# stm32.net
KiCad netlist of a schematic drawn in Altium Designer
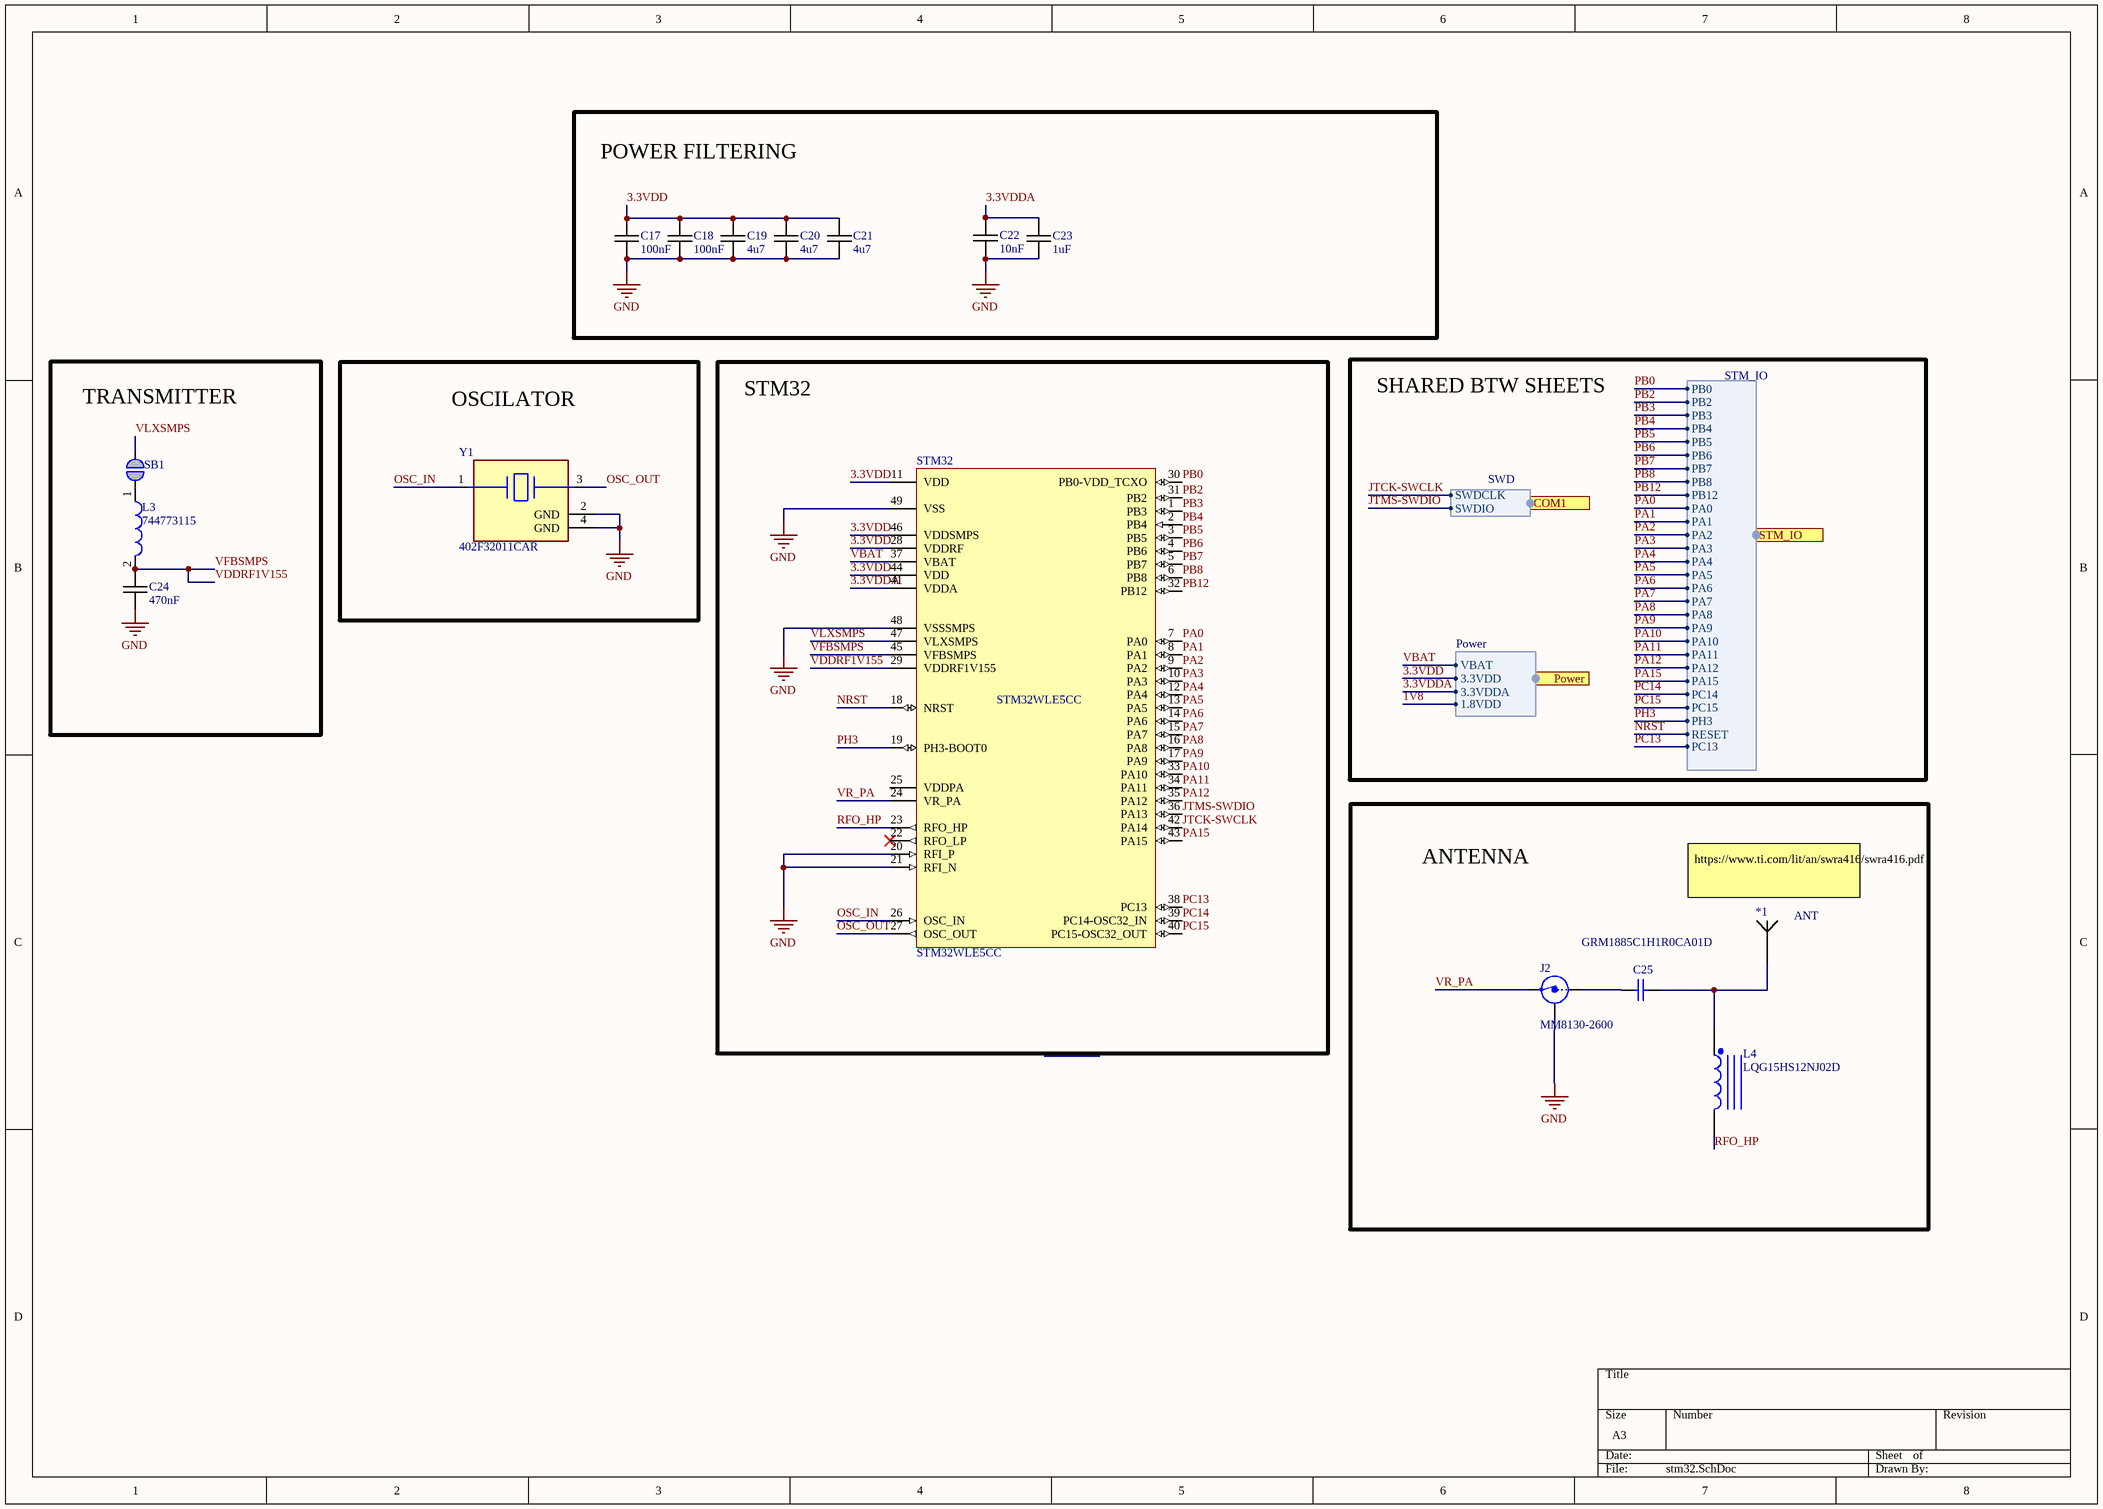
[diagram p0: stm32.SchDoc]

(export (version "E")
  (design (tool "Eeschema 10.0.6"))
  (components
    (comp (ref "*1") (value "ANT") (libsource (lib "FEEL-Lora-STM32-Road-datalogger") (part "ANT")))
    (comp (ref "C17")
      (value "100nF")
      (footprint "0603C-GENERIC")
      (description "CAPACITOR 0603 CERAMIC")
      (fields (field (name "TOLERANCE") "±10%") (field (name "MANUFACTURER PART NUMBER") "C1608X7R1H103K"))
      (libsource (lib "vh_altium_library") (part "0603C-100NF-50V-X7R-TDK"))
    )
    (comp (ref "C18")
      (value "100nF")
      (footprint "0603C-GENERIC")
      (description "CAPACITOR 0603 CERAMIC")
      (fields (field (name "TOLERANCE") "±10%") (field (name "MANUFACTURER PART NUMBER") "C1608X7R1H103K"))
      (libsource (lib "vh_altium_library") (part "0603C-100NF-50V-X7R-TDK"))
    )
    (comp (ref "C19")
      (value "4u7")
      (footprint "0603C-GENERIC")
      (description "CAPACITOR 0603 CERAMIC")
      (libsource (lib "vh_altium_library") (part "0603C-4U7-6V3-X5R-KEM"))
    )
    (comp (ref "C20")
      (value "4u7")
      (footprint "0603C-GENERIC")
      (description "CAPACITOR 0603 CERAMIC")
      (libsource (lib "vh_altium_library") (part "0603C-4U7-6V3-X5R-KEM"))
    )
    (comp (ref "C21")
      (value "4u7")
      (footprint "0603C-GENERIC")
      (description "CAPACITOR 0603 CERAMIC")
      (libsource (lib "vh_altium_library") (part "0603C-4U7-6V3-X5R-KEM"))
    )
    (comp (ref "C22")
      (value "10nF")
      (footprint "0603C-GENERIC")
      (description "CAPACITOR 0603 CERAMIC")
      (fields
        (field (name "MANUFACTURER PART NUMBER") "GRM188R71H103KA01D")
        (field (name "MANUFACTURER") "Murata Electronics North America")
      )
      (libsource (lib "vh_altium_library") (part "0603C-10NF-50V-X7R-MUR"))
    )
    (comp (ref "C23")
      (value "1uF")
      (footprint "0603C-GENERIC")
      (description "CAPACITOR 0603 CERAMIC")
      (libsource (lib "vh_altium_library") (part "0603C-1UF-25V-X5R-SAM"))
    )
    (comp (ref "C24")
      (value "470nF")
      (footprint "0603C-GENERIC")
      (description "CAPACITOR 0603 CERAMIC")
      (fields
        (field (name "MANUFACTURER") "Murata Electronics North America")
        (field (name "TOLERANCE") "±10%")
      )
      (libsource (lib "vh_altium_library") (part "0603C-470NF-25V-X7R-MUR"))
    )
    (comp (ref "C25")
      (value "GRM1885C1H1R0CA01D")
      (footprint "CAPC1608X90X35NL10T15")
      (fields (field (name "MANUFACTURER") "Murata"))
      (libsource (lib "Altium Content Vault") (part "CAP"))
    )
    (comp (ref "J2")
      (value "MM8130-2600")
      (footprint "COAXIAL-SWF")
      (description "Coaxial Connector with Switch")
      (fields (field (name "MANUFACTURER") "Murata") (field (name "PUBLISHER") "Nordic Semiconductor"))
      (libsource (lib "FEEL2020") (part "MM8130-2600"))
    )
    (comp (ref "L3")
      (value "744773115")
      (footprint "WE-PD2-S")
      (description "SMD Power Inductor WE-PD2, L = 15.0 µH")
      (libsource (lib "Altium Content Vault") (part "PAS-IND-INDUCTOR-2"))
    )
    (comp (ref "L4")
      (value "LQG15HS12NJ02D")
      (footprint "INDC1005X55X25LL05T10_A")
      (description "Chip Inductor, 12 nH, +/-5%, 300 mA, -55 to 125 degC, 0402 (1005 Metric), RoHS, Tape and Reel")
      (fields (field (name "MANUFACTURER") "Murata"))
      (libsource (lib "Altium Content Vault") (part "IND-DOT-2"))
    )
    (comp (ref "SB1")
      (value "Solderbridge")
      (footprint "Solderbridge")
      (fields (field (name "PUBLISHER") "Nordic Semiconductor"))
      (libsource (lib "FEEL2020") (part "SOLDERBRIDGE"))
    )
    (comp (ref "STM32")
      (value "STM32WLE5CC")
      (footprint "stm32wle5cc")
      (description "Ultra-low power multi-modulation wireless STM32WLE5 microcontrollers")
      (libsource (lib "FEEL-Lora-STM32-Road-datalogger") (part "STM32WLE5CC"))
    )
    (comp (ref "Y1")
      (value "402F32011CAR")
      (footprint "FP-402-MFG")
      (description "CRYSTAL 32.0000MHZ 10PF SMD")
      (fields (field (name "TOLERANCE") "10ppm"))
      (libsource (lib "Altium Content Vault") (part "aa2bcc763e4d5c877d8ff97ea4c95a3"))
    )
  )
  (nets
    (net (code "5") (name "/3.3VDD") (class "Default")
      (node (ref "C17") (pin "1") (pintype "passive"))
      (node (ref "C18") (pin "1") (pintype "passive"))
      (node (ref "C19") (pin "1") (pintype "passive"))
      (node (ref "C20") (pin "1") (pintype "passive"))
      (node (ref "C21") (pin "1") (pintype "passive"))
      (node (ref "STM32") (pin "11") (pinfunction "VDD_11") (pintype "power_in"))
      (node (ref "STM32") (pin "28") (pinfunction "VDDRF_28") (pintype "power_in"))
      (node (ref "STM32") (pin "44") (pinfunction "VDD_44") (pintype "power_in"))
      (node (ref "STM32") (pin "46") (pinfunction "VDDSMPS_46") (pintype "power_in"))
    )
    (net (code "6") (name "/3.3VDDA") (class "Default")
      (node (ref "C22") (pin "1") (pintype "passive"))
      (node (ref "C23") (pin "1") (pintype "passive"))
      (node (ref "STM32") (pin "41") (pinfunction "VDDA_41") (pintype "power_in"))
    )
    (net (code "7") (name "/JTCK-SWCLK") (class "Default")
      (node (ref "STM32") (pin "42") (pinfunction "PA14_42") (pintype "bidirectional"))
    )
    (net (code "8") (name "/JTMS-SWDIO") (class "Default")
      (node (ref "STM32") (pin "36") (pinfunction "PA13_36") (pintype "bidirectional"))
    )
    (net (code "9") (name "/NRST") (class "Default")
      (node (ref "STM32") (pin "18") (pinfunction "NRST_18") (pintype "bidirectional"))
    )
    (net (code "10") (name "/OSC_IN") (class "Default")
      (node (ref "STM32") (pin "26") (pinfunction "OSC_IN_26") (pintype "input"))
      (node (ref "Y1") (pin "1") (pinfunction "1_1") (pintype "passive"))
    )
    (net (code "11") (name "/OSC_OUT") (class "Default")
      (node (ref "STM32") (pin "27") (pinfunction "OSC_OUT_27") (pintype "output"))
      (node (ref "Y1") (pin "3") (pinfunction "3_3") (pintype "passive"))
    )
    (net (code "12") (name "/PA0") (class "Default")
      (node (ref "STM32") (pin "7") (pinfunction "PA0_7") (pintype "bidirectional"))
    )
    (net (code "13") (name "/PA1") (class "Default")
      (node (ref "STM32") (pin "8") (pinfunction "PA1_8") (pintype "bidirectional"))
    )
    (net (code "14") (name "/PA2") (class "Default")
      (node (ref "STM32") (pin "9") (pinfunction "PA2_9") (pintype "bidirectional"))
    )
    (net (code "15") (name "/PA3") (class "Default")
      (node (ref "STM32") (pin "10") (pinfunction "PA3_10") (pintype "bidirectional"))
    )
    (net (code "16") (name "/PA4") (class "Default")
      (node (ref "STM32") (pin "12") (pinfunction "PA4_12") (pintype "bidirectional"))
    )
    (net (code "17") (name "/PA5") (class "Default")
      (node (ref "STM32") (pin "13") (pinfunction "PA5_13") (pintype "bidirectional"))
    )
    (net (code "18") (name "/PA6") (class "Default")
      (node (ref "STM32") (pin "14") (pinfunction "PA6_14") (pintype "bidirectional"))
    )
    (net (code "19") (name "/PA7") (class "Default")
      (node (ref "STM32") (pin "15") (pinfunction "PA7_15") (pintype "bidirectional"))
    )
    (net (code "20") (name "/PA8") (class "Default")
      (node (ref "STM32") (pin "16") (pinfunction "PA8_16") (pintype "bidirectional"))
    )
    (net (code "21") (name "/PA9") (class "Default")
      (node (ref "STM32") (pin "17") (pinfunction "PA9_17") (pintype "bidirectional"))
    )
    (net (code "22") (name "/PA10") (class "Default")
      (node (ref "STM32") (pin "33") (pinfunction "PA10_33") (pintype "bidirectional"))
    )
    (net (code "23") (name "/PA11") (class "Default")
      (node (ref "STM32") (pin "34") (pinfunction "PA11_34") (pintype "bidirectional"))
    )
    (net (code "24") (name "/PA12") (class "Default")
      (node (ref "STM32") (pin "35") (pinfunction "PA12_35") (pintype "bidirectional"))
    )
    (net (code "25") (name "/PA15") (class "Default")
      (node (ref "STM32") (pin "43") (pinfunction "PA15_43") (pintype "bidirectional"))
    )
    (net (code "26") (name "/PB0") (class "Default")
      (node (ref "STM32") (pin "30") (pinfunction "PB0-VDD_TCXO_30") (pintype "bidirectional"))
    )
    (net (code "27") (name "/PB2") (class "Default")
      (node (ref "STM32") (pin "31") (pinfunction "PB2_31") (pintype "bidirectional"))
    )
    (net (code "28") (name "/PB3") (class "Default")
      (node (ref "STM32") (pin "1") (pinfunction "PB3_1") (pintype "bidirectional"))
    )
    (net (code "29") (name "/PB4") (class "Default")
      (node (ref "STM32") (pin "2") (pinfunction "PB4_2") (pintype "input"))
    )
    (net (code "30") (name "/PB5") (class "Default")
      (node (ref "STM32") (pin "3") (pinfunction "PB5_3") (pintype "bidirectional"))
    )
    (net (code "31") (name "/PB6") (class "Default")
      (node (ref "STM32") (pin "4") (pinfunction "PB6_4") (pintype "bidirectional"))
    )
    (net (code "32") (name "/PB7") (class "Default")
      (node (ref "STM32") (pin "5") (pinfunction "PB7_5") (pintype "bidirectional"))
    )
    (net (code "33") (name "/PB8") (class "Default")
      (node (ref "STM32") (pin "6") (pinfunction "PB8_6") (pintype "bidirectional"))
    )
    (net (code "34") (name "/PB12") (class "Default")
      (node (ref "STM32") (pin "32") (pinfunction "PB12_32") (pintype "bidirectional"))
    )
    (net (code "35") (name "/PC13") (class "Default")
      (node (ref "STM32") (pin "38") (pinfunction "PC13_38") (pintype "bidirectional"))
    )
    (net (code "36") (name "/PC14") (class "Default")
      (node (ref "STM32") (pin "39") (pinfunction "PC14-OSC32_IN_39") (pintype "bidirectional"))
    )
    (net (code "37") (name "/PC15") (class "Default")
      (node (ref "STM32") (pin "40") (pinfunction "PC15-OSC32_OUT_40") (pintype "bidirectional"))
    )
    (net (code "38") (name "/PH3") (class "Default")
      (node (ref "STM32") (pin "19") (pinfunction "PH3-BOOT0_19") (pintype "bidirectional"))
    )
    (net (code "39") (name "/RFO_HP") (class "Default")
      (node (ref "L4") (pin "2") (pinfunction "2_2") (pintype "passive"))
      (node (ref "STM32") (pin "23") (pinfunction "RFO_HP_23") (pintype "output"))
    )
    (net (code "40") (name "/VBAT") (class "Default")
      (node (ref "STM32") (pin "37") (pinfunction "VBAT_37") (pintype "power_in"))
    )
    (net (code "41") (name "/VDDRF1V155") (class "Default")
      (node (ref "C24") (pin "1") (pintype "passive"))
      (node (ref "L3") (pin "2") (pinfunction "2_2") (pintype "passive"))
      (node (ref "STM32") (pin "29") (pinfunction "VDDRF1V155_29") (pintype "power_in"))
      (node (ref "STM32") (pin "45") (pinfunction "VFBSMPS_45") (pintype "power_in"))
    )
    (net (code "42") (name "/VLXSMPS") (class "Default")
      (node (ref "SB1") (pin "1") (pinfunction "0_1") (pintype "passive"))
      (node (ref "STM32") (pin "47") (pinfunction "VLXSMPS_47") (pintype "power_in"))
    )
    (net (code "43") (name "/VR_PA") (class "Default")
      (node (ref "J2") (pin "3") (pinfunction "OUT_3") (pintype "passive"))
      (node (ref "STM32") (pin "24") (pinfunction "VR_PA_24") (pintype "power_in"))
    )
    (net (code "47") (name "GND") (class "Default")
      (node (ref "C17") (pin "2") (pintype "passive"))
      (node (ref "C18") (pin "2") (pintype "passive"))
      (node (ref "C19") (pin "2") (pintype "passive"))
      (node (ref "C20") (pin "2") (pintype "passive"))
      (node (ref "C21") (pin "2") (pintype "passive"))
      (node (ref "C22") (pin "2") (pintype "passive"))
      (node (ref "C23") (pin "2") (pintype "passive"))
      (node (ref "C24") (pin "2") (pintype "passive"))
      (node (ref "J2") (pin "2") (pinfunction "Shield_2") (pintype "passive"))
      (node (ref "STM32") (pin "20") (pinfunction "RFI_P_20") (pintype "input"))
      (node (ref "STM32") (pin "21") (pinfunction "RFI_N_21") (pintype "input"))
      (node (ref "STM32") (pin "48") (pinfunction "VSSSMPS_48") (pintype "power_in"))
      (node (ref "STM32") (pin "49") (pinfunction "VSS_49") (pintype "power_in"))
      (node (ref "Y1") (pin "2") (pinfunction "GND_2") (pintype "power_in"))
      (node (ref "Y1") (pin "4") (pinfunction "GND_4") (pintype "power_in"))
    )
    (net (code "48") (name "Net-(*1-Pad1)") (class "Default")
      (node (ref "*1") (pin "1") (pinfunction "1_1") (pintype "passive"))
      (node (ref "C25") (pin "2") (pinfunction "2_2") (pintype "passive"))
      (node (ref "L4") (pin "1") (pinfunction "1_1") (pintype "passive"))
    )
    (net (code "49") (name "Net-(J2-IN)") (class "Default")
      (node (ref "C25") (pin "1") (pinfunction "1_1") (pintype "passive"))
      (node (ref "J2") (pin "1") (pinfunction "IN_1") (pintype "passive"))
    )
    (net (code "50") (name "Net-(SB1-1)") (class "Default")
      (node (ref "L3") (pin "1") (pinfunction "1_1") (pintype "passive"))
      (node (ref "SB1") (pin "2") (pinfunction "1_2") (pintype "passive"))
    )
    (net (code "51") (name "unconnected-(STM32-RFO_LP-Pad22)") (class "Default")
      (node (ref "STM32") (pin "22") (pinfunction "RFO_LP_22") (pintype "output+no_connect"))
    )
    (net (code "52") (name "unconnected-(STM32-VDDPA-Pad25)") (class "Default")
      (node (ref "STM32") (pin "25") (pinfunction "VDDPA_25") (pintype "power_in"))
    )
  )
)
